# krajBB-Moj_i__Matej.net
KiCad netlist of a schematic drawn in EAGLE
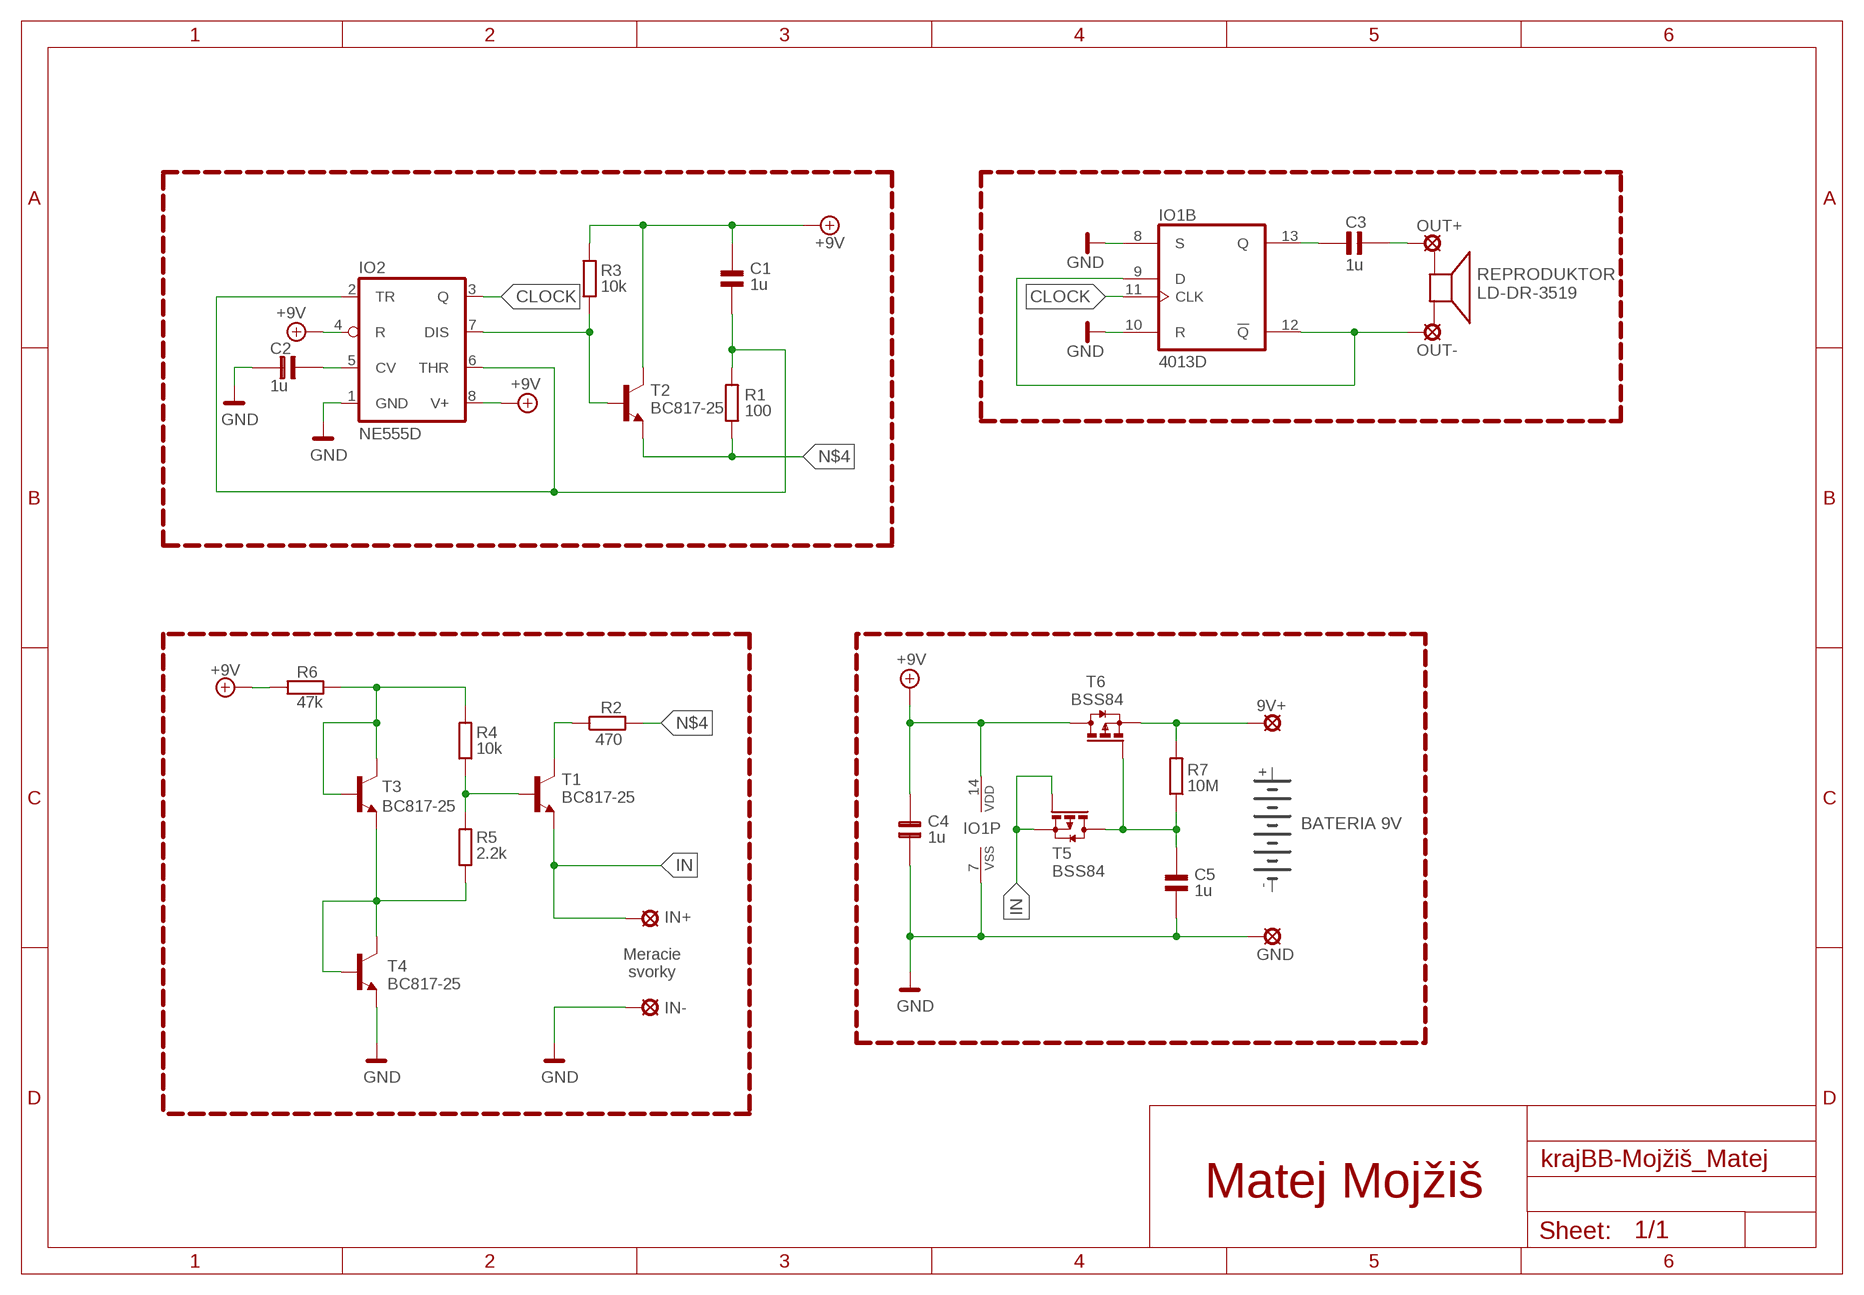
[diagram p0: schematic, sheet 1]

(export (version "E")
  (design (tool "Eeschema 10.0.6"))
  (components
    (comp (ref "9V+")
      (value "SMD3X3")
      (footprint "eagle-import:SMD3X3")
      (libsource (lib "eagle-import") (part "SMD3X3"))
    )
    (comp (ref "C1")
      (value "1u")
      (footprint "eagle-import:1206")
      (libsource (lib "eagle-import") (part "C1206TOP"))
    )
    (comp (ref "C2")
      (value "1u")
      (footprint "eagle-import:1206")
      (libsource (lib "eagle-import") (part "C1206TOP"))
    )
    (comp (ref "C3")
      (value "1u")
      (footprint "eagle-import:1206")
      (libsource (lib "eagle-import") (part "C1206TOP"))
    )
    (comp (ref "C4")
      (value "1u")
      (footprint "eagle-import:1206")
      (libsource (lib "eagle-import") (part "C1206TOP"))
    )
    (comp (ref "C5")
      (value "1u")
      (footprint "eagle-import:1206")
      (libsource (lib "eagle-import") (part "C1206TOP"))
    )
    (comp (ref "GND")
      (value "SMD3X3")
      (footprint "eagle-import:SMD3X3")
      (libsource (lib "eagle-import") (part "SMD3X3"))
    )
    (comp (ref "IN+")
      (value "SMD3X3")
      (footprint "eagle-import:SMD3X3")
      (libsource (lib "eagle-import") (part "SMD3X3"))
    )
    (comp (ref "IN-")
      (value "SMD3X3")
      (footprint "eagle-import:SMD3X3")
      (libsource (lib "eagle-import") (part "SMD3X3"))
    )
    (comp (ref "IO1")
      (value "4013D")
      (footprint "eagle-import:SO14")
      (libsource (lib "eagle-import") (part "4013D"))
    )
    (comp (ref "IO2")
      (value "NE555D")
      (footprint "eagle-import:SO08")
      (libsource (lib "eagle-import") (part "555DNE"))
    )
    (comp (ref "OUT+")
      (value "SMD3X3")
      (footprint "eagle-import:SMD3X3")
      (libsource (lib "eagle-import") (part "SMD3X3"))
    )
    (comp (ref "OUT-")
      (value "SMD3X3")
      (footprint "eagle-import:SMD3X3")
      (libsource (lib "eagle-import") (part "SMD3X3"))
    )
    (comp (ref "R1")
      (value "100")
      (footprint "eagle-import:1206")
      (libsource (lib "eagle-import") (part "R1206TOP"))
    )
    (comp (ref "R2")
      (value "470")
      (footprint "eagle-import:1206")
      (libsource (lib "eagle-import") (part "R1206TOP"))
    )
    (comp (ref "R3")
      (value "10k")
      (footprint "eagle-import:1206")
      (libsource (lib "eagle-import") (part "R1206TOP"))
    )
    (comp (ref "R4")
      (value "10k")
      (footprint "eagle-import:1206")
      (libsource (lib "eagle-import") (part "R1206TOP"))
    )
    (comp (ref "R5")
      (value "2.2k")
      (footprint "eagle-import:1206")
      (libsource (lib "eagle-import") (part "R1206TOP"))
    )
    (comp (ref "R6")
      (value "47k")
      (footprint "eagle-import:1206")
      (libsource (lib "eagle-import") (part "R1206TOP"))
    )
    (comp (ref "R7")
      (value "10M")
      (footprint "eagle-import:1206")
      (libsource (lib "eagle-import") (part "R1206TOP"))
    )
    (comp (ref "REPRODUKTOR")
      (value "LD-DR-3519")
      (footprint "eagle-import:LD-DR-3519")
      (libsource (lib "eagle-import") (part "LD-DR-3519"))
    )
    (comp (ref "T1")
      (value "BC817-25")
      (footprint "eagle-import:SOT23-BEC")
      (libsource (lib "eagle-import") (part "BC817SMD-25"))
    )
    (comp (ref "T2")
      (value "BC817-25")
      (footprint "eagle-import:SOT23-BEC")
      (libsource (lib "eagle-import") (part "BC817SMD-25"))
    )
    (comp (ref "T3")
      (value "BC817-25")
      (footprint "eagle-import:SOT23-BEC")
      (libsource (lib "eagle-import") (part "BC817SMD-25"))
    )
    (comp (ref "T4")
      (value "BC817-25")
      (footprint "eagle-import:SOT23-BEC")
      (libsource (lib "eagle-import") (part "BC817SMD-25"))
    )
    (comp (ref "T5")
      (value "BSS84")
      (footprint "eagle-import:SOT23")
      (libsource (lib "eagle-import") (part "BSS84"))
    )
    (comp (ref "T6")
      (value "BSS84")
      (footprint "eagle-import:SOT23")
      (libsource (lib "eagle-import") (part "BSS84"))
    )
    (comp (ref "U$1")
      (value "9VBATTERY")
      (footprint "eagle-import:9VBATTERY")
      (libsource (lib "eagle-import") (part "9VBATTERY"))
    )
  )
  (nets
    (net (code "1") (name "+9V") (class "Default")
      (node (ref "C1") (pin "2") (pinfunction "2_2") (pintype "passive"))
      (node (ref "C4") (pin "2") (pinfunction "2_2") (pintype "passive"))
      (node (ref "IO1") (pin "14") (pinfunction "VDD_14") (pintype "power_in"))
      (node (ref "IO2") (pin "4") (pinfunction "R_4") (pintype "input"))
      (node (ref "IO2") (pin "8") (pinfunction "V+_8") (pintype "power_in"))
      (node (ref "R3") (pin "2") (pinfunction "2_2") (pintype "passive"))
      (node (ref "R6") (pin "2") (pinfunction "2_2") (pintype "passive"))
      (node (ref "T2") (pin "C") (pinfunction "C_C") (pintype "passive"))
      (node (ref "T6") (pin "3") (pinfunction "D_3") (pintype "passive"))
    )
    (net (code "2") (name "CLOCK") (class "Default")
      (node (ref "IO1") (pin "11") (pinfunction "CLK_11") (pintype "input"))
      (node (ref "IO2") (pin "3") (pinfunction "Q_3") (pintype "output"))
    )
    (net (code "3") (name "GND") (class "Default")
      (node (ref "C2") (pin "1") (pinfunction "1_1") (pintype "passive"))
      (node (ref "C4") (pin "1") (pinfunction "1_1") (pintype "passive"))
      (node (ref "C5") (pin "1") (pinfunction "1_1") (pintype "passive"))
      (node (ref "GND") (pin "P$1") (pinfunction "MP_P$1") (pintype "passive"))
      (node (ref "IN-") (pin "P$1") (pinfunction "MP_P$1") (pintype "passive"))
      (node (ref "IO1") (pin "10") (pinfunction "R_10") (pintype "input"))
      (node (ref "IO1") (pin "7") (pinfunction "VSS_7") (pintype "power_in"))
      (node (ref "IO1") (pin "8") (pinfunction "S_8") (pintype "input"))
      (node (ref "IO2") (pin "1") (pinfunction "GND_1") (pintype "power_in"))
      (node (ref "T4") (pin "E") (pinfunction "E_E") (pintype "passive"))
    )
    (net (code "4") (name "IN") (class "Default")
      (node (ref "IN+") (pin "P$1") (pinfunction "MP_P$1") (pintype "passive"))
      (node (ref "T1") (pin "E") (pinfunction "E_E") (pintype "passive"))
      (node (ref "T5") (pin "1") (pinfunction "G_1") (pintype "passive"))
      (node (ref "T5") (pin "2") (pinfunction "S_2") (pintype "passive"))
    )
    (net (code "5") (name "N$4") (class "Default")
      (node (ref "R1") (pin "1") (pinfunction "1_1") (pintype "passive"))
      (node (ref "R2") (pin "2") (pinfunction "2_2") (pintype "passive"))
      (node (ref "T2") (pin "E") (pinfunction "E_E") (pintype "passive"))
    )
    (net (code "6") (name "Net-(9V+-MP)") (class "Default")
      (node (ref "9V+") (pin "P$1") (pinfunction "MP_P$1") (pintype "passive"))
      (node (ref "R7") (pin "2") (pinfunction "2_2") (pintype "passive"))
      (node (ref "T6") (pin "2") (pinfunction "S_2") (pintype "passive"))
    )
    (net (code "7") (name "Net-(IO1B-D)") (class "Default")
      (node (ref "IO1") (pin "12") (pinfunction "~{Q}_12") (pintype "output"))
      (node (ref "IO1") (pin "9") (pinfunction "D_9") (pintype "input"))
      (node (ref "OUT-") (pin "P$1") (pinfunction "MP_P$1") (pintype "passive"))
    )
    (net (code "8") (name "Net-(IO1B-Q)") (class "Default")
      (node (ref "C3") (pin "1") (pinfunction "1_1") (pintype "passive"))
      (node (ref "IO1") (pin "13") (pinfunction "Q_13") (pintype "output"))
    )
    (net (code "9") (name "Net-(IO2-CV)") (class "Default")
      (node (ref "C2") (pin "2") (pinfunction "2_2") (pintype "passive"))
      (node (ref "IO2") (pin "5") (pinfunction "CV_5") (pintype "input"))
    )
    (net (code "10") (name "Net-(IO2-DIS)") (class "Default")
      (node (ref "IO2") (pin "7") (pinfunction "DIS_7") (pintype "input"))
      (node (ref "R3") (pin "1") (pinfunction "1_1") (pintype "passive"))
      (node (ref "T2") (pin "B") (pinfunction "B_B") (pintype "passive"))
    )
    (net (code "11") (name "Net-(IO2-THR)") (class "Default")
      (node (ref "C1") (pin "1") (pinfunction "1_1") (pintype "passive"))
      (node (ref "IO2") (pin "2") (pinfunction "TR_2") (pintype "input"))
      (node (ref "IO2") (pin "6") (pinfunction "THR_6") (pintype "input"))
      (node (ref "R1") (pin "2") (pinfunction "2_2") (pintype "passive"))
    )
    (net (code "12") (name "Net-(OUT+-MP)") (class "Default")
      (node (ref "C3") (pin "2") (pinfunction "2_2") (pintype "passive"))
      (node (ref "OUT+") (pin "P$1") (pinfunction "MP_P$1") (pintype "passive"))
    )
    (net (code "13") (name "Net-(R2-Pad1)") (class "Default")
      (node (ref "R2") (pin "1") (pinfunction "1_1") (pintype "passive"))
      (node (ref "T1") (pin "C") (pinfunction "C_C") (pintype "passive"))
    )
    (net (code "14") (name "Net-(R4-Pad1)") (class "Default")
      (node (ref "R4") (pin "1") (pinfunction "1_1") (pintype "passive"))
      (node (ref "R5") (pin "2") (pinfunction "2_2") (pintype "passive"))
      (node (ref "T1") (pin "B") (pinfunction "B_B") (pintype "passive"))
    )
    (net (code "15") (name "Net-(R4-Pad2)") (class "Default")
      (node (ref "R4") (pin "2") (pinfunction "2_2") (pintype "passive"))
      (node (ref "R6") (pin "1") (pinfunction "1_1") (pintype "passive"))
      (node (ref "T3") (pin "B") (pinfunction "B_B") (pintype "passive"))
      (node (ref "T3") (pin "C") (pinfunction "C_C") (pintype "passive"))
    )
    (net (code "16") (name "Net-(R5-Pad1)") (class "Default")
      (node (ref "R5") (pin "1") (pinfunction "1_1") (pintype "passive"))
      (node (ref "T3") (pin "E") (pinfunction "E_E") (pintype "passive"))
      (node (ref "T4") (pin "B") (pinfunction "B_B") (pintype "passive"))
      (node (ref "T4") (pin "C") (pinfunction "C_C") (pintype "passive"))
    )
    (net (code "17") (name "Net-(T5-D)") (class "Default")
      (node (ref "C5") (pin "2") (pinfunction "2_2") (pintype "passive"))
      (node (ref "R7") (pin "1") (pinfunction "1_1") (pintype "passive"))
      (node (ref "T5") (pin "3") (pinfunction "D_3") (pintype "passive"))
      (node (ref "T6") (pin "1") (pinfunction "G_1") (pintype "passive"))
    )
    (net (code "18") (name "unconnected-(REPRODUKTOR-1-PadP$1)") (class "Default")
      (node (ref "REPRODUKTOR") (pin "P$1") (pinfunction "1_P$1") (pintype "passive"))
    )
    (net (code "19") (name "unconnected-(REPRODUKTOR-2-PadP$2)") (class "Default")
      (node (ref "REPRODUKTOR") (pin "P$2") (pinfunction "2_P$2") (pintype "passive"))
    )
  )
)
